# B4_FM_-Z_SOLAR_PANEL.net
KiCad netlist of a schematic drawn in EAGLE
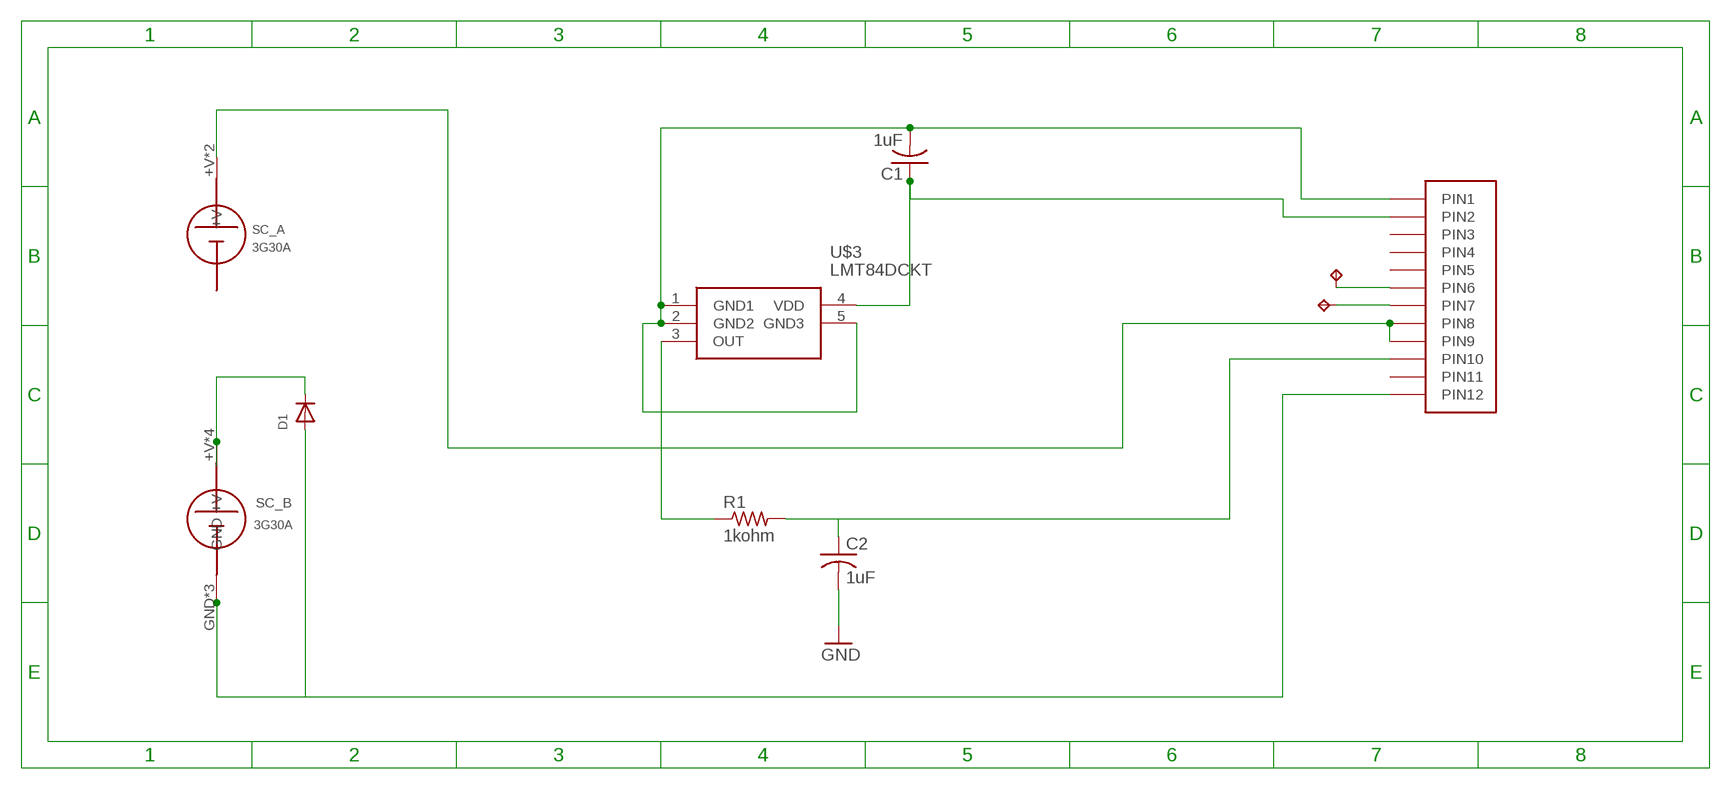
[diagram p0: schematic, sheet 1]

(export (version "E")
  (design (tool "Eeschema 10.0.6"))
  (components
    (comp (ref "C1")
      (value "1uF")
      (footprint "eagle-import:C0805")
      (libsource (lib "eagle-import") (part "C-USC0805"))
    )
    (comp (ref "C2")
      (value "1uF")
      (footprint "eagle-import:C0805")
      (libsource (lib "eagle-import") (part "C-USC0805"))
    )
    (comp (ref "D1")
      (value "DIODE_SOD-123FL")
      (footprint "eagle-import:SOD-123FL")
      (libsource (lib "eagle-import") (part "DIODE_SOD-123FL"))
    )
    (comp (ref "R1")
      (value "1kohm")
      (footprint "eagle-import:R0402")
      (libsource (lib "eagle-import") (part "R-US_R0402"))
    )
    (comp (ref "SDA1")
      (value "S1751-46R")
      (footprint "eagle-import:S1751-46R")
      (libsource (lib "eagle-import") (part "S1751-46R"))
    )
    (comp (ref "SDA2")
      (value "S1751-46R")
      (footprint "eagle-import:S1751-46R")
      (libsource (lib "eagle-import") (part "S1751-46R"))
    )
    (comp (ref "U$1")
      (value "HEADER12PIN")
      (footprint "eagle-import:HEADER12PIN")
      (libsource (lib "eagle-import") (part "HEADER12PIN"))
    )
    (comp (ref "U$3")
      (value "LMT84DCKT")
      (footprint "eagle-import:SOT65P210X110-5N")
      (fields (field (name "RS_PART_NUMBER") "8115860"))
      (libsource (lib "eagle-import") (part "LMT84DCKT"))
    )
    (comp (ref "U$4")
      (value "SC_A")
      (footprint "eagle-import:SC_A")
      (libsource (lib "eagle-import") (part "SC_A"))
    )
    (comp (ref "U$5")
      (value "SC_B")
      (footprint "eagle-import:SC_B")
      (libsource (lib "eagle-import") (part "SC_B"))
    )
  )
  (nets
    (net (code "1") (name "GND") (class "Default")
      (node (ref "C1") (pin "2") (pinfunction "2_2") (pintype "passive"))
      (node (ref "C2") (pin "2") (pinfunction "2_2") (pintype "passive"))
      (node (ref "D1") (pin "A") (pinfunction "A_A") (pintype "passive"))
      (node (ref "U$1") (pin "P1") (pinfunction "PIN1_P1") (pintype "bidirectional"))
      (node (ref "U$1") (pin "P12") (pinfunction "PIN12_P12") (pintype "bidirectional"))
      (node (ref "U$3") (pin "1") (pinfunction "GND1_1") (pintype "power_in"))
      (node (ref "U$3") (pin "2") (pinfunction "GND2_2") (pintype "power_in"))
      (node (ref "U$3") (pin "5") (pinfunction "GND3_5") (pintype "power_in"))
      (node (ref "U$5") (pin "GND") (pinfunction "GND_GND") (pintype "bidirectional"))
      (node (ref "U$5") (pin "GND1") (pinfunction "GND_GND1") (pintype "bidirectional"))
      (node (ref "U$5") (pin "GND2") (pinfunction "GND_GND2") (pintype "bidirectional"))
    )
    (net (code "2") (name "Net-(D1-PadC)") (class "Default")
      (node (ref "D1") (pin "C") (pinfunction "C_C") (pintype "passive"))
      (node (ref "U$5") (pin "+V") (pinfunction "+V_+V") (pintype "bidirectional"))
      (node (ref "U$5") (pin "+V2") (pinfunction "+V_+V2") (pintype "bidirectional"))
      (node (ref "U$5") (pin "+V3") (pinfunction "+V_+V3") (pintype "bidirectional"))
      (node (ref "U$5") (pin "+V4") (pinfunction "+V_+V4") (pintype "bidirectional"))
    )
    (net (code "3") (name "Net-(SDA1-TP)") (class "Default")
      (node (ref "SDA1") (pin "P$1") (pinfunction "TP_P$1") (pintype "input"))
      (node (ref "U$1") (pin "P6") (pinfunction "PIN6_P6") (pintype "bidirectional"))
    )
    (net (code "4") (name "Net-(SDA2-TP)") (class "Default")
      (node (ref "SDA2") (pin "P$1") (pinfunction "TP_P$1") (pintype "input"))
      (node (ref "U$1") (pin "P7") (pinfunction "PIN7_P7") (pintype "bidirectional"))
    )
    (net (code "5") (name "Net-(U$1-PIN2)") (class "Default")
      (node (ref "C1") (pin "1") (pinfunction "1_1") (pintype "passive"))
      (node (ref "U$1") (pin "P2") (pinfunction "PIN2_P2") (pintype "bidirectional"))
      (node (ref "U$3") (pin "4") (pinfunction "VDD_4") (pintype "power_in"))
    )
    (net (code "6") (name "Net-(U$1-PIN8)") (class "Default")
      (node (ref "U$1") (pin "P8") (pinfunction "PIN8_P8") (pintype "bidirectional"))
      (node (ref "U$1") (pin "P9") (pinfunction "PIN9_P9") (pintype "bidirectional"))
      (node (ref "U$4") (pin "+V") (pinfunction "+V_+V") (pintype "bidirectional"))
      (node (ref "U$4") (pin "+V1") (pinfunction "+V_+V1") (pintype "bidirectional"))
    )
    (net (code "7") (name "Net-(U$1-PIN10)") (class "Default")
      (node (ref "C2") (pin "1") (pinfunction "1_1") (pintype "passive"))
      (node (ref "R1") (pin "2") (pinfunction "2_2") (pintype "passive"))
      (node (ref "U$1") (pin "P10") (pinfunction "PIN10_P10") (pintype "bidirectional"))
    )
    (net (code "8") (name "Net-(U$3-OUT)") (class "Default")
      (node (ref "R1") (pin "1") (pinfunction "1_1") (pintype "passive"))
      (node (ref "U$3") (pin "3") (pinfunction "OUT_3") (pintype "output"))
    )
    (net (code "9") (name "unconnected-(U$1-PIN3-PadP3)") (class "Default")
      (node (ref "U$1") (pin "P3") (pinfunction "PIN3_P3") (pintype "bidirectional"))
    )
    (net (code "10") (name "unconnected-(U$1-PIN4-PadP4)") (class "Default")
      (node (ref "U$1") (pin "P4") (pinfunction "PIN4_P4") (pintype "bidirectional"))
    )
    (net (code "11") (name "unconnected-(U$1-PIN5-PadP5)") (class "Default")
      (node (ref "U$1") (pin "P5") (pinfunction "PIN5_P5") (pintype "bidirectional"))
    )
    (net (code "12") (name "unconnected-(U$1-PIN11-PadP11)") (class "Default")
      (node (ref "U$1") (pin "P11") (pinfunction "PIN11_P11") (pintype "bidirectional"))
    )
  )
)
